# Display70_Cape.net
KiCad netlist of a schematic drawn in EAGLE
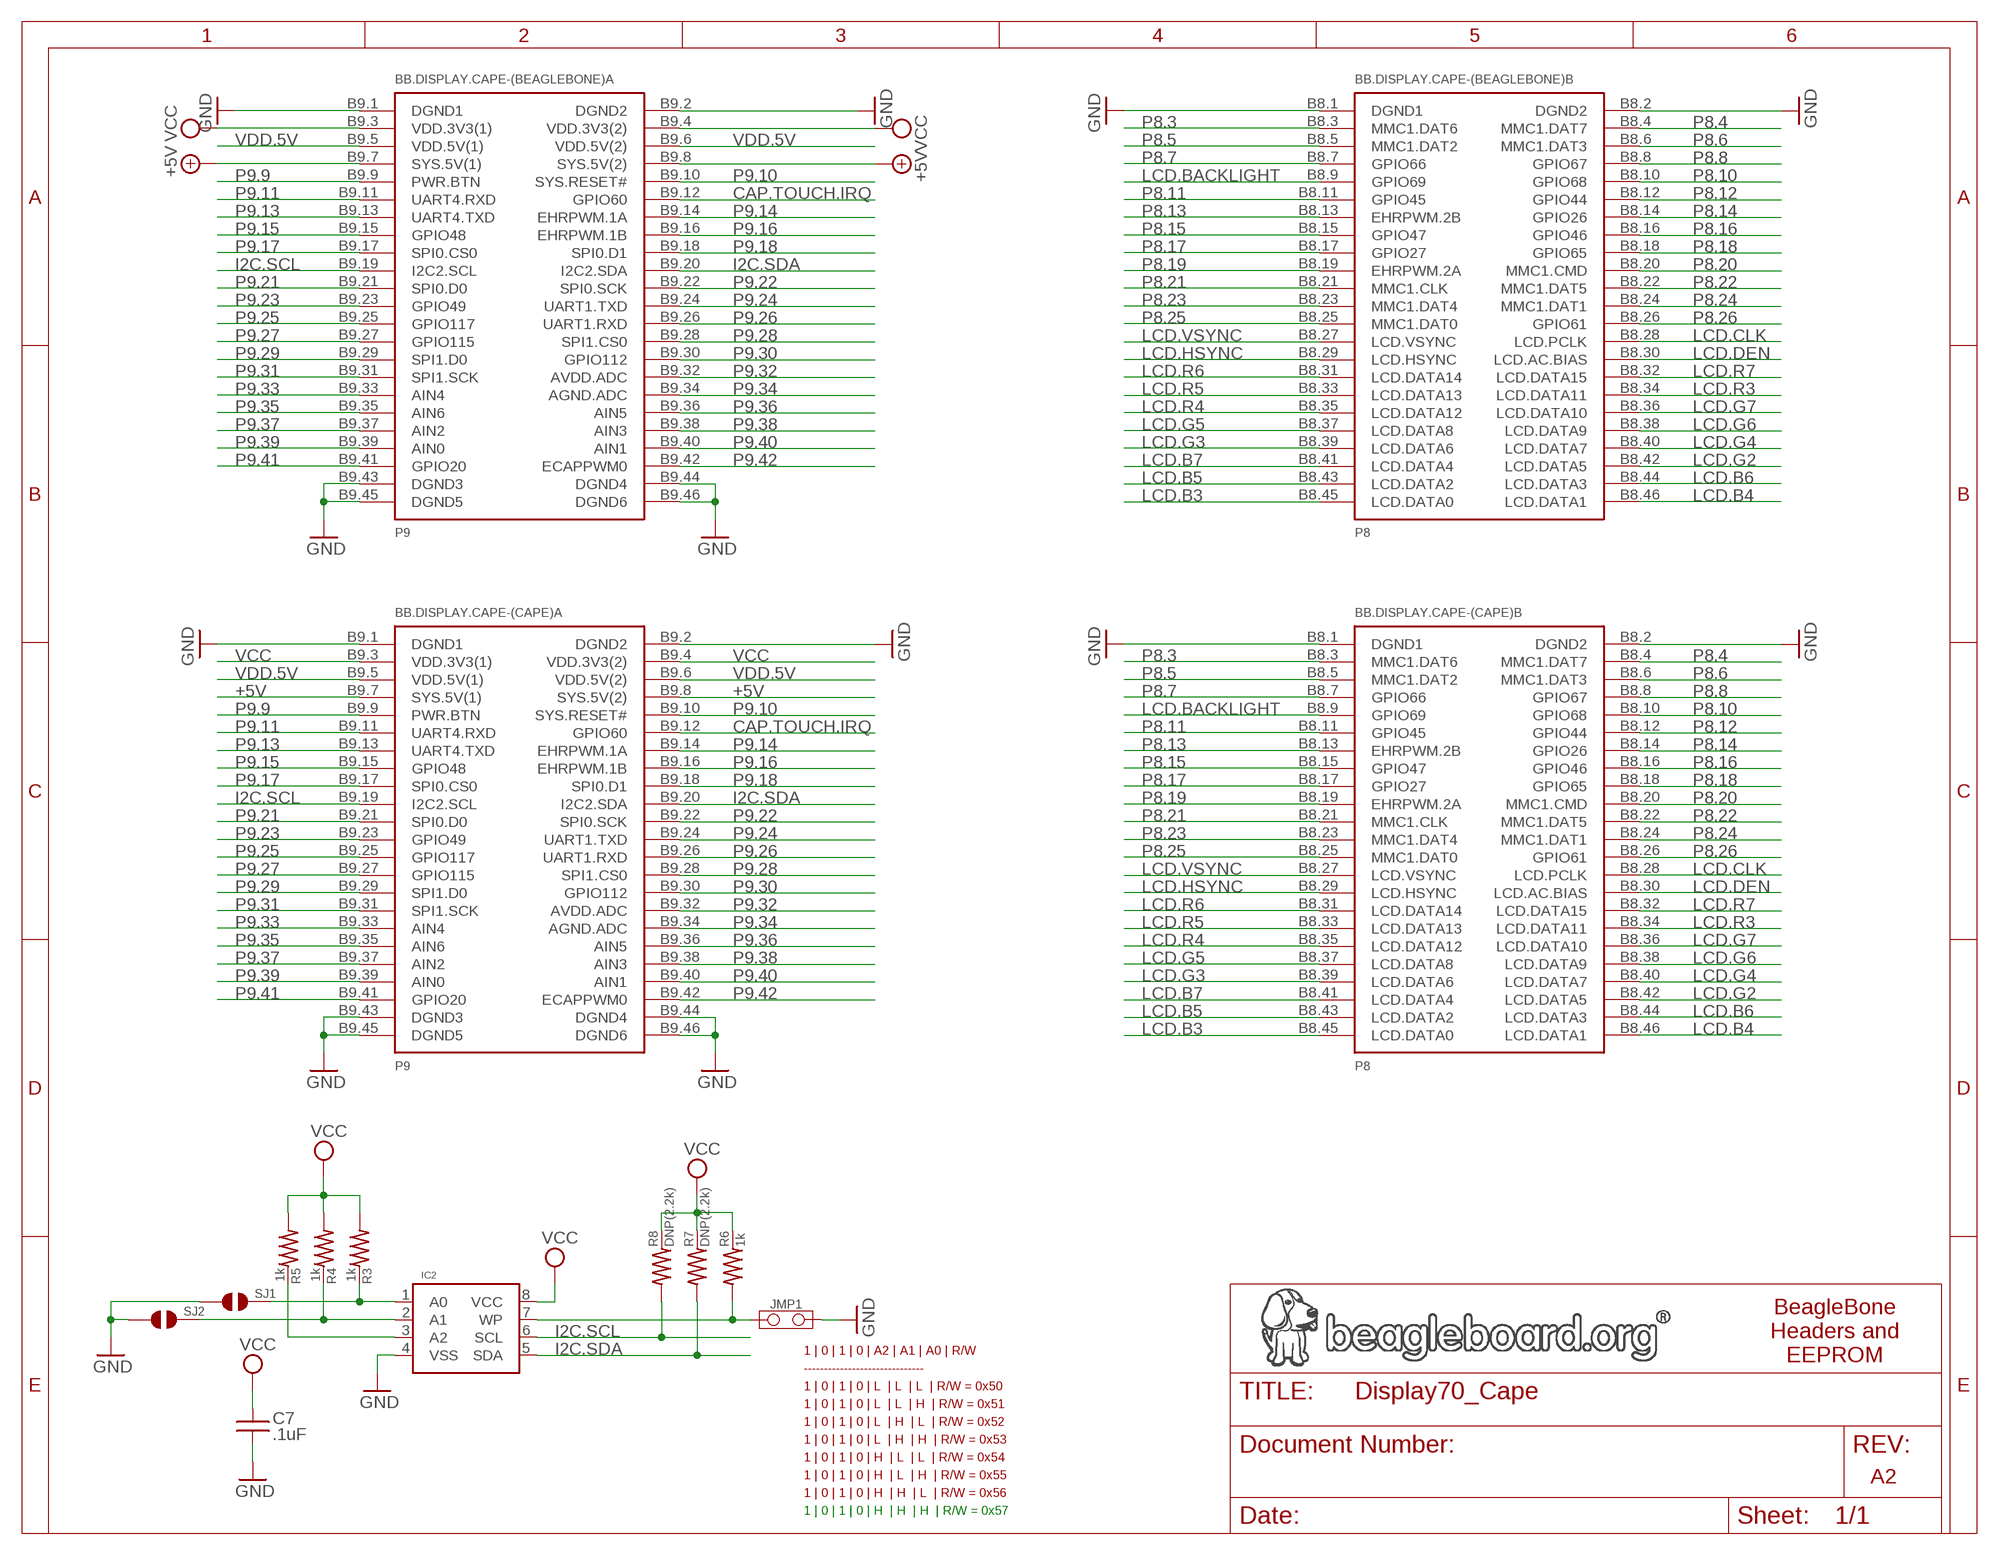
[diagram p0: schematic, sheet 1, part 1 of 2]
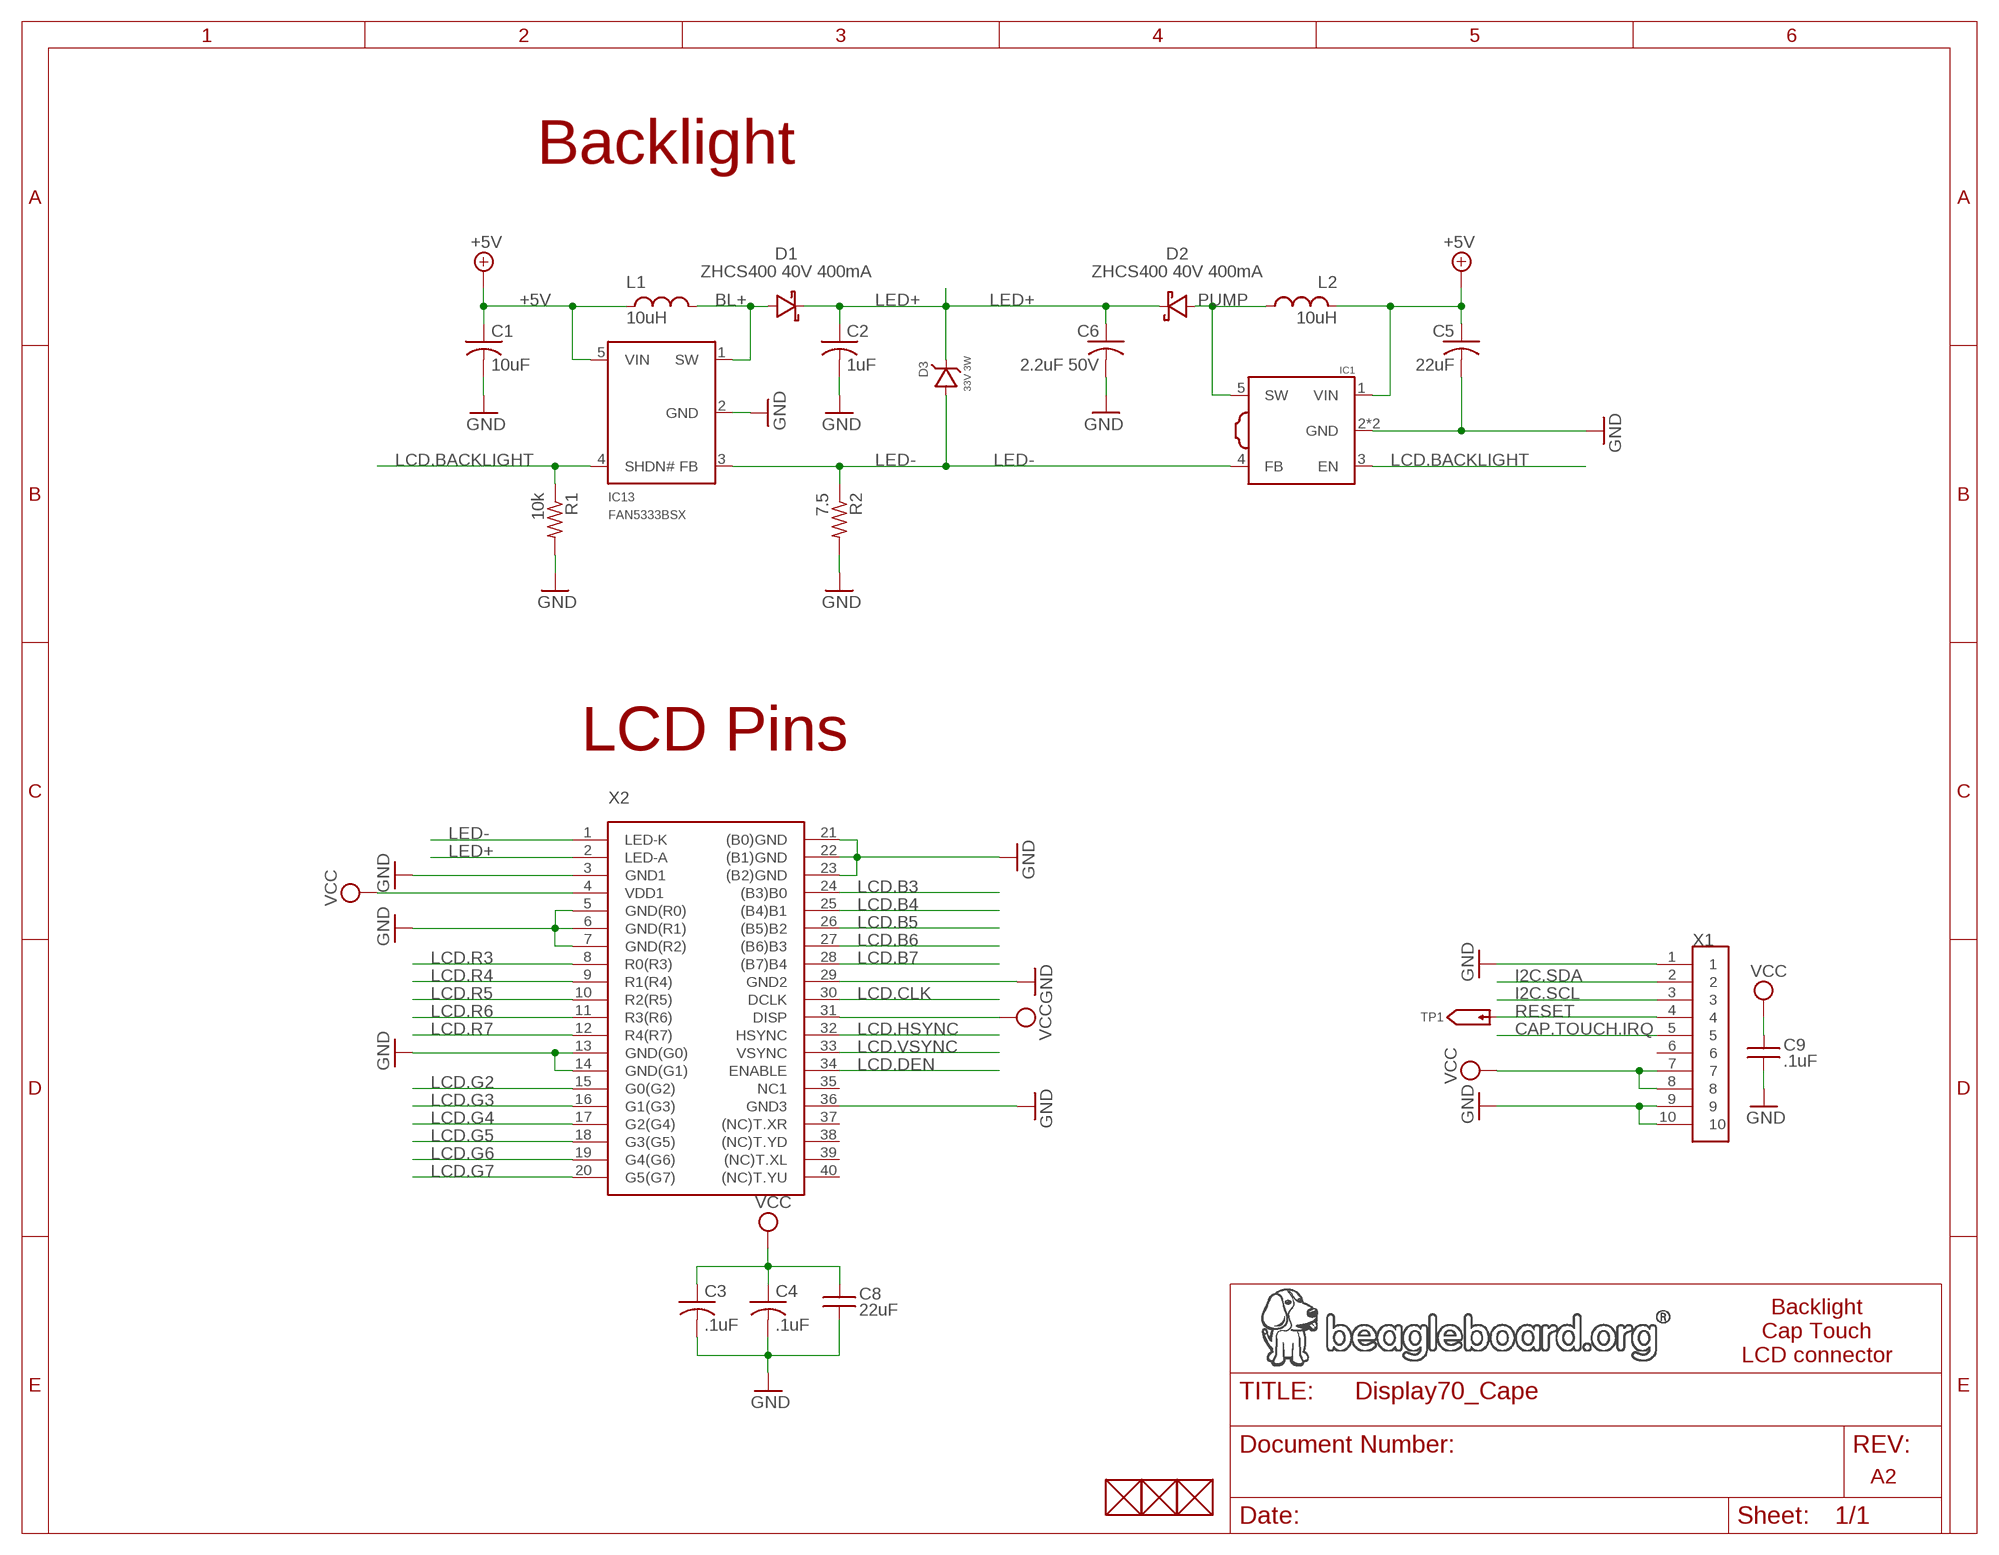
[diagram p1: schematic, sheet 1, part 2 of 2]

(export (version "E")
  (design (tool "Eeschema 10.0.6"))
  (components
    (comp (ref "BB.DISPLAY.CAPE-(BEAGLEBONE)")
      (value "BEAGLEBONE.CAPE.DISPLAY-7.BEAGLEBONE")
      (footprint "eagle-import:BEAGLEBONE.CAPE.DISPLAY-7.BEAGLEBONE")
      (libsource (lib "eagle-import") (part "BEAGLEBONE.CAPE.DISPLAY-7.BEAGLEBONE"))
    )
    (comp (ref "BB.DISPLAY.CAPE-(CAPE)")
      (value "BEAGLEBONE.CAPE.DISPLAY-7.CAPE")
      (footprint "eagle-import:BEAGLEBONE.CAPE.DISPLAY-7.CAPE")
      (libsource (lib "eagle-import") (part "BEAGLEBONE.CAPE.DISPLAY-7.CAPE"))
    )
    (comp (ref "C1")
      (value "10uF")
      (footprint "eagle-import:C0603K")
      (libsource (lib "eagle-import") (part "C-USC0603K"))
    )
    (comp (ref "C2")
      (value "1uF")
      (footprint "eagle-import:C0805K")
      (libsource (lib "eagle-import") (part "C-USC0805K"))
    )
    (comp (ref "C3")
      (value ".1uF")
      (footprint "eagle-import:C0402K")
      (libsource (lib "eagle-import") (part "C-USC0402K"))
    )
    (comp (ref "C4")
      (value ".1uF")
      (footprint "eagle-import:C0402K")
      (libsource (lib "eagle-import") (part "C-USC0402K"))
    )
    (comp (ref "C5")
      (value "22uF")
      (footprint "eagle-import:C0805K")
      (libsource (lib "eagle-import") (part "C-USC0805K"))
    )
    (comp (ref "C6")
      (value "2.2uF 50V")
      (footprint "eagle-import:C0805K")
      (libsource (lib "eagle-import") (part "C-USC0805K"))
    )
    (comp (ref "C7")
      (value ".1uF")
      (footprint "eagle-import:0402")
      (libsource (lib "eagle-import") (part "CAPACITOR-(INCH)-0402"))
    )
    (comp (ref "C8")
      (value "22uF")
      (footprint "eagle-import:0805")
      (libsource (lib "eagle-import") (part "CAPACITOR-(INCH)-0805"))
    )
    (comp (ref "C9")
      (value ".1uF")
      (footprint "eagle-import:0402")
      (libsource (lib "eagle-import") (part "CAPACITOR-(INCH)-0402"))
    )
    (comp (ref "D1")
      (value "ZHCS400 40V 400mA")
      (footprint "eagle-import:SOD323(NXP)WAVE")
      (libsource (lib "eagle-import") (part "DIODE-SCHOTTKY-(NXP)-SOD323-(WAVE)"))
    )
    (comp (ref "D2")
      (value "ZHCS400 40V 400mA")
      (footprint "eagle-import:SOD323(NXP)WAVE")
      (libsource (lib "eagle-import") (part "DIODE-SCHOTTKY-(NXP)-SOD323-(WAVE)"))
    )
    (comp (ref "D3")
      (value "33V 3W")
      (footprint "eagle-import:SMB(ON.SEMI)")
      (libsource (lib "eagle-import") (part "DIODE-ZENER-"))
    )
    (comp (ref "FUD1")
      (value "FIDUCIAL")
      (footprint "eagle-import:FIDUCIAL_40MIL")
      (libsource (lib "eagle-import") (part "FIDUCIAL"))
    )
    (comp (ref "FUD2")
      (value "FIDUCIAL")
      (footprint "eagle-import:FIDUCIAL_40MIL")
      (libsource (lib "eagle-import") (part "FIDUCIAL"))
    )
    (comp (ref "FUD3")
      (value "FIDUCIAL")
      (footprint "eagle-import:FIDUCIAL_40MIL")
      (libsource (lib "eagle-import") (part "FIDUCIAL"))
    )
    (comp (ref "IC1")
      (value "PT4110")
      (footprint "eagle-import:SOT89-5(DIODES)")
      (libsource (lib "eagle-import") (part "PT4110"))
    )
    (comp (ref "IC2")
      (value "CAT24C32")
      (footprint "eagle-import:UDFN8,2X3(ON-SEMI)")
      (libsource (lib "eagle-import") (part "CAT24C32"))
    )
    (comp (ref "IC13")
      (value "FAN5333BSX")
      (footprint "eagle-import:SOT23-5(FAIRCHILD)")
      (libsource (lib "eagle-import") (part "FAN533X"))
    )
    (comp (ref "JMP1")
      (value "JUMPER-(X2)")
      (footprint "eagle-import:JUMPER-(X2)")
      (libsource (lib "eagle-import") (part "JUMPER-(X2)"))
    )
    (comp (ref "L1")
      (value "10uH")
      (footprint "eagle-import:NRS(TAIYO.YUDEN)")
      (libsource (lib "eagle-import") (part "INDUCTOR-(TAIYO-YUDEN)-NRS5030"))
    )
    (comp (ref "L2")
      (value "10uH")
      (footprint "eagle-import:NRS(TAIYO.YUDEN)")
      (libsource (lib "eagle-import") (part "INDUCTOR-(TAIYO-YUDEN)-NRS5030"))
    )
    (comp (ref "R1")
      (value "10k")
      (footprint "eagle-import:R0603")
      (libsource (lib "eagle-import") (part "R-US_R0603"))
    )
    (comp (ref "R2")
      (value "7.5")
      (footprint "eagle-import:R0603")
      (libsource (lib "eagle-import") (part "R-US_R0603"))
    )
    (comp (ref "R3")
      (value "1k")
      (footprint "eagle-import:0402")
      (libsource (lib "eagle-import") (part "RESISTOR-(INCH)-0402"))
    )
    (comp (ref "R4")
      (value "1k")
      (footprint "eagle-import:0402")
      (libsource (lib "eagle-import") (part "RESISTOR-(INCH)-0402"))
    )
    (comp (ref "R5")
      (value "1k")
      (footprint "eagle-import:0402")
      (libsource (lib "eagle-import") (part "RESISTOR-(INCH)-0402"))
    )
    (comp (ref "R6")
      (value "1k")
      (footprint "eagle-import:0402")
      (libsource (lib "eagle-import") (part "RESISTOR-(INCH)-0402"))
    )
    (comp (ref "R7")
      (value "DNP(2.2k)")
      (footprint "eagle-import:0402")
      (libsource (lib "eagle-import") (part "RESISTOR-(INCH)-0402"))
    )
    (comp (ref "R8")
      (value "DNP(2.2k)")
      (footprint "eagle-import:0402")
      (libsource (lib "eagle-import") (part "RESISTOR-(INCH)-0402"))
    )
    (comp (ref "SJ1")
      (value "SOLDER.JOINT-(INCH)-0402")
      (footprint "eagle-import:SOLDER.JOINT(0402)")
      (libsource (lib "eagle-import") (part "SOLDER.JOINT-(INCH)-0402"))
    )
    (comp (ref "SJ2")
      (value "SOLDER.JOINT-(INCH)-0402")
      (footprint "eagle-import:SOLDER.JOINT(0402)")
      (libsource (lib "eagle-import") (part "SOLDER.JOINT-(INCH)-0402"))
    )
    (comp (ref "TP1")
      (value "TESTPAD/W_HOLE_1X1")
      (footprint "eagle-import:TESTPAD_W_HOLE_1X1")
      (libsource (lib "eagle-import") (part "TESTPAD/W_HOLE_1X1"))
    )
    (comp (ref "X1")
      (value "10-PIN-(0.5MM-PITCH)-FPC-CONNECTOR")
      (footprint "eagle-import:10-PIN-(0.5MM-PITCH)-FPC-CONNECTOR")
      (libsource (lib "eagle-import") (part "10-PIN-(0.5MM-PITCH)-FPC-CONNECTOR"))
    )
    (comp (ref "X2")
      (value "LCD-40PIN_FFC/FPC_0.5MM_PITCH")
      (footprint "eagle-import:KISD04-40_T1_E")
      (libsource (lib "eagle-import") (part "LCD-40PIN_FFC/FPC_0.5MM_PITCH"))
    )
  )
  (nets
    (net (code "1") (name "+5V") (class "Default")
      (node (ref "BB.DISPLAY.CAPE-(BEAGLEBONE)") (pin "B9.7") (pinfunction "SYS.5V(1)_B9.7") (pintype "bidirectional"))
      (node (ref "BB.DISPLAY.CAPE-(BEAGLEBONE)") (pin "B9.8") (pinfunction "SYS.5V(2)_B9.8") (pintype "bidirectional"))
      (node (ref "BB.DISPLAY.CAPE-(CAPE)") (pin "B9.7") (pinfunction "SYS.5V(1)_B9.7") (pintype "bidirectional"))
      (node (ref "BB.DISPLAY.CAPE-(CAPE)") (pin "B9.8") (pinfunction "SYS.5V(2)_B9.8") (pintype "bidirectional"))
      (node (ref "C1") (pin "1") (pinfunction "1_1") (pintype "passive"))
      (node (ref "C5") (pin "1") (pinfunction "1_1") (pintype "passive"))
      (node (ref "IC1") (pin "1") (pinfunction "VIN_1") (pintype "bidirectional"))
      (node (ref "IC13") (pin "5") (pinfunction "VIN_5") (pintype "bidirectional"))
      (node (ref "L1") (pin "1") (pinfunction "1_1") (pintype "bidirectional"))
      (node (ref "L2") (pin "1") (pinfunction "1_1") (pintype "bidirectional"))
    )
    (net (code "2") (name "/BL+") (class "Default")
      (node (ref "D1") (pin "A") (pinfunction "ANODE_A") (pintype "bidirectional"))
      (node (ref "IC13") (pin "1") (pinfunction "SW_1") (pintype "bidirectional"))
      (node (ref "L1") (pin "2") (pinfunction "2_2") (pintype "bidirectional"))
    )
    (net (code "3") (name "/CAP.TOUCH.IRQ") (class "Default")
      (node (ref "BB.DISPLAY.CAPE-(BEAGLEBONE)") (pin "B9.12") (pinfunction "GPIO60_B9.12") (pintype "bidirectional"))
      (node (ref "BB.DISPLAY.CAPE-(CAPE)") (pin "B9.12") (pinfunction "GPIO60_B9.12") (pintype "bidirectional"))
      (node (ref "X1") (pin "5") (pinfunction "5_5") (pintype "bidirectional"))
    )
    (net (code "4") (name "/I2C.SCL") (class "Default")
      (node (ref "BB.DISPLAY.CAPE-(BEAGLEBONE)") (pin "B9.19") (pinfunction "I2C2.SCL_B9.19") (pintype "bidirectional"))
      (node (ref "BB.DISPLAY.CAPE-(CAPE)") (pin "B9.19") (pinfunction "I2C2.SCL_B9.19") (pintype "bidirectional"))
      (node (ref "IC2") (pin "6") (pinfunction "SCL_6") (pintype "bidirectional"))
      (node (ref "R8") (pin "1") (pinfunction "1_1") (pintype "bidirectional"))
      (node (ref "X1") (pin "3") (pinfunction "3_3") (pintype "bidirectional"))
    )
    (net (code "5") (name "/I2C.SDA") (class "Default")
      (node (ref "BB.DISPLAY.CAPE-(BEAGLEBONE)") (pin "B9.20") (pinfunction "I2C2.SDA_B9.20") (pintype "bidirectional"))
      (node (ref "BB.DISPLAY.CAPE-(CAPE)") (pin "B9.20") (pinfunction "I2C2.SDA_B9.20") (pintype "bidirectional"))
      (node (ref "IC2") (pin "5") (pinfunction "SDA_5") (pintype "bidirectional"))
      (node (ref "R7") (pin "1") (pinfunction "1_1") (pintype "bidirectional"))
      (node (ref "X1") (pin "2") (pinfunction "2_2") (pintype "bidirectional"))
    )
    (net (code "6") (name "/LCD.B3") (class "Default")
      (node (ref "BB.DISPLAY.CAPE-(BEAGLEBONE)") (pin "B8.45") (pinfunction "LCD.DATA0_B8.45") (pintype "bidirectional"))
      (node (ref "BB.DISPLAY.CAPE-(CAPE)") (pin "B8.45") (pinfunction "LCD.DATA0_B8.45") (pintype "bidirectional"))
      (node (ref "X2") (pin "24") (pinfunction "(B3)B0_24") (pintype "bidirectional"))
    )
    (net (code "7") (name "/LCD.B4") (class "Default")
      (node (ref "BB.DISPLAY.CAPE-(BEAGLEBONE)") (pin "B8.46") (pinfunction "LCD.DATA1_B8.46") (pintype "bidirectional"))
      (node (ref "BB.DISPLAY.CAPE-(CAPE)") (pin "B8.46") (pinfunction "LCD.DATA1_B8.46") (pintype "bidirectional"))
      (node (ref "X2") (pin "25") (pinfunction "(B4)B1_25") (pintype "bidirectional"))
    )
    (net (code "8") (name "/LCD.B5") (class "Default")
      (node (ref "BB.DISPLAY.CAPE-(BEAGLEBONE)") (pin "B8.43") (pinfunction "LCD.DATA2_B8.43") (pintype "bidirectional"))
      (node (ref "BB.DISPLAY.CAPE-(CAPE)") (pin "B8.43") (pinfunction "LCD.DATA2_B8.43") (pintype "bidirectional"))
      (node (ref "X2") (pin "26") (pinfunction "(B5)B2_26") (pintype "bidirectional"))
    )
    (net (code "9") (name "/LCD.B6") (class "Default")
      (node (ref "BB.DISPLAY.CAPE-(BEAGLEBONE)") (pin "B8.44") (pinfunction "LCD.DATA3_B8.44") (pintype "bidirectional"))
      (node (ref "BB.DISPLAY.CAPE-(CAPE)") (pin "B8.44") (pinfunction "LCD.DATA3_B8.44") (pintype "bidirectional"))
      (node (ref "X2") (pin "27") (pinfunction "(B6)B3_27") (pintype "bidirectional"))
    )
    (net (code "10") (name "/LCD.B7") (class "Default")
      (node (ref "BB.DISPLAY.CAPE-(BEAGLEBONE)") (pin "B8.41") (pinfunction "LCD.DATA4_B8.41") (pintype "bidirectional"))
      (node (ref "BB.DISPLAY.CAPE-(CAPE)") (pin "B8.41") (pinfunction "LCD.DATA4_B8.41") (pintype "bidirectional"))
      (node (ref "X2") (pin "28") (pinfunction "(B7)B4_28") (pintype "bidirectional"))
    )
    (net (code "11") (name "/LCD.BACKLIGHT") (class "Default")
      (node (ref "BB.DISPLAY.CAPE-(BEAGLEBONE)") (pin "B8.9") (pinfunction "GPIO69_B8.9") (pintype "bidirectional"))
      (node (ref "BB.DISPLAY.CAPE-(CAPE)") (pin "B8.9") (pinfunction "GPIO69_B8.9") (pintype "bidirectional"))
      (node (ref "IC1") (pin "3") (pinfunction "EN_3") (pintype "bidirectional"))
      (node (ref "IC13") (pin "4") (pinfunction "SHDN#_4") (pintype "bidirectional"))
      (node (ref "R1") (pin "1") (pinfunction "1_1") (pintype "passive"))
    )
    (net (code "12") (name "/LCD.CLK") (class "Default")
      (node (ref "BB.DISPLAY.CAPE-(BEAGLEBONE)") (pin "B8.28") (pinfunction "LCD.PCLK_B8.28") (pintype "bidirectional"))
      (node (ref "BB.DISPLAY.CAPE-(CAPE)") (pin "B8.28") (pinfunction "LCD.PCLK_B8.28") (pintype "bidirectional"))
      (node (ref "X2") (pin "30") (pinfunction "DCLK_30") (pintype "bidirectional"))
    )
    (net (code "13") (name "/LCD.DEN") (class "Default")
      (node (ref "BB.DISPLAY.CAPE-(BEAGLEBONE)") (pin "B8.30") (pinfunction "LCD.AC.BIAS_B8.30") (pintype "bidirectional"))
      (node (ref "BB.DISPLAY.CAPE-(CAPE)") (pin "B8.30") (pinfunction "LCD.AC.BIAS_B8.30") (pintype "bidirectional"))
      (node (ref "X2") (pin "34") (pinfunction "ENABLE_34") (pintype "bidirectional"))
    )
    (net (code "14") (name "/LCD.G2") (class "Default")
      (node (ref "BB.DISPLAY.CAPE-(BEAGLEBONE)") (pin "B8.42") (pinfunction "LCD.DATA5_B8.42") (pintype "bidirectional"))
      (node (ref "BB.DISPLAY.CAPE-(CAPE)") (pin "B8.42") (pinfunction "LCD.DATA5_B8.42") (pintype "bidirectional"))
      (node (ref "X2") (pin "15") (pinfunction "G0(G2)_15") (pintype "bidirectional"))
    )
    (net (code "15") (name "/LCD.G3") (class "Default")
      (node (ref "BB.DISPLAY.CAPE-(BEAGLEBONE)") (pin "B8.39") (pinfunction "LCD.DATA6_B8.39") (pintype "bidirectional"))
      (node (ref "BB.DISPLAY.CAPE-(CAPE)") (pin "B8.39") (pinfunction "LCD.DATA6_B8.39") (pintype "bidirectional"))
      (node (ref "X2") (pin "16") (pinfunction "G1(G3)_16") (pintype "bidirectional"))
    )
    (net (code "16") (name "/LCD.G4") (class "Default")
      (node (ref "BB.DISPLAY.CAPE-(BEAGLEBONE)") (pin "B8.40") (pinfunction "LCD.DATA7_B8.40") (pintype "bidirectional"))
      (node (ref "BB.DISPLAY.CAPE-(CAPE)") (pin "B8.40") (pinfunction "LCD.DATA7_B8.40") (pintype "bidirectional"))
      (node (ref "X2") (pin "17") (pinfunction "G2(G4)_17") (pintype "bidirectional"))
    )
    (net (code "17") (name "/LCD.G5") (class "Default")
      (node (ref "BB.DISPLAY.CAPE-(BEAGLEBONE)") (pin "B8.37") (pinfunction "LCD.DATA8_B8.37") (pintype "bidirectional"))
      (node (ref "BB.DISPLAY.CAPE-(CAPE)") (pin "B8.37") (pinfunction "LCD.DATA8_B8.37") (pintype "bidirectional"))
      (node (ref "X2") (pin "18") (pinfunction "G3(G5)_18") (pintype "bidirectional"))
    )
    (net (code "18") (name "/LCD.G6") (class "Default")
      (node (ref "BB.DISPLAY.CAPE-(BEAGLEBONE)") (pin "B8.38") (pinfunction "LCD.DATA9_B8.38") (pintype "bidirectional"))
      (node (ref "BB.DISPLAY.CAPE-(CAPE)") (pin "B8.38") (pinfunction "LCD.DATA9_B8.38") (pintype "bidirectional"))
      (node (ref "X2") (pin "19") (pinfunction "G4(G6)_19") (pintype "bidirectional"))
    )
    (net (code "19") (name "/LCD.G7") (class "Default")
      (node (ref "BB.DISPLAY.CAPE-(BEAGLEBONE)") (pin "B8.36") (pinfunction "LCD.DATA10_B8.36") (pintype "bidirectional"))
      (node (ref "BB.DISPLAY.CAPE-(CAPE)") (pin "B8.36") (pinfunction "LCD.DATA10_B8.36") (pintype "bidirectional"))
      (node (ref "X2") (pin "20") (pinfunction "G5(G7)_20") (pintype "bidirectional"))
    )
    (net (code "20") (name "/LCD.HSYNC") (class "Default")
      (node (ref "BB.DISPLAY.CAPE-(BEAGLEBONE)") (pin "B8.29") (pinfunction "LCD.HSYNC_B8.29") (pintype "bidirectional"))
      (node (ref "BB.DISPLAY.CAPE-(CAPE)") (pin "B8.29") (pinfunction "LCD.HSYNC_B8.29") (pintype "bidirectional"))
      (node (ref "X2") (pin "32") (pinfunction "HSYNC_32") (pintype "bidirectional"))
    )
    (net (code "21") (name "/LCD.R3") (class "Default")
      (node (ref "BB.DISPLAY.CAPE-(BEAGLEBONE)") (pin "B8.34") (pinfunction "LCD.DATA11_B8.34") (pintype "bidirectional"))
      (node (ref "BB.DISPLAY.CAPE-(CAPE)") (pin "B8.34") (pinfunction "LCD.DATA11_B8.34") (pintype "bidirectional"))
      (node (ref "X2") (pin "8") (pinfunction "R0(R3)_8") (pintype "bidirectional"))
    )
    (net (code "22") (name "/LCD.R4") (class "Default")
      (node (ref "BB.DISPLAY.CAPE-(BEAGLEBONE)") (pin "B8.35") (pinfunction "LCD.DATA12_B8.35") (pintype "bidirectional"))
      (node (ref "BB.DISPLAY.CAPE-(CAPE)") (pin "B8.35") (pinfunction "LCD.DATA12_B8.35") (pintype "bidirectional"))
      (node (ref "X2") (pin "9") (pinfunction "R1(R4)_9") (pintype "bidirectional"))
    )
    (net (code "23") (name "/LCD.R5") (class "Default")
      (node (ref "BB.DISPLAY.CAPE-(BEAGLEBONE)") (pin "B8.33") (pinfunction "LCD.DATA13_B8.33") (pintype "bidirectional"))
      (node (ref "BB.DISPLAY.CAPE-(CAPE)") (pin "B8.33") (pinfunction "LCD.DATA13_B8.33") (pintype "bidirectional"))
      (node (ref "X2") (pin "10") (pinfunction "R2(R5)_10") (pintype "bidirectional"))
    )
    (net (code "24") (name "/LCD.R6") (class "Default")
      (node (ref "BB.DISPLAY.CAPE-(BEAGLEBONE)") (pin "B8.31") (pinfunction "LCD.DATA14_B8.31") (pintype "bidirectional"))
      (node (ref "BB.DISPLAY.CAPE-(CAPE)") (pin "B8.31") (pinfunction "LCD.DATA14_B8.31") (pintype "bidirectional"))
      (node (ref "X2") (pin "11") (pinfunction "R3(R6)_11") (pintype "bidirectional"))
    )
    (net (code "25") (name "/LCD.R7") (class "Default")
      (node (ref "BB.DISPLAY.CAPE-(BEAGLEBONE)") (pin "B8.32") (pinfunction "LCD.DATA15_B8.32") (pintype "bidirectional"))
      (node (ref "BB.DISPLAY.CAPE-(CAPE)") (pin "B8.32") (pinfunction "LCD.DATA15_B8.32") (pintype "bidirectional"))
      (node (ref "X2") (pin "12") (pinfunction "R4(R7)_12") (pintype "bidirectional"))
    )
    (net (code "26") (name "/LCD.VSYNC") (class "Default")
      (node (ref "BB.DISPLAY.CAPE-(BEAGLEBONE)") (pin "B8.27") (pinfunction "LCD.VSYNC_B8.27") (pintype "bidirectional"))
      (node (ref "BB.DISPLAY.CAPE-(CAPE)") (pin "B8.27") (pinfunction "LCD.VSYNC_B8.27") (pintype "bidirectional"))
      (node (ref "X2") (pin "33") (pinfunction "VSYNC_33") (pintype "bidirectional"))
    )
    (net (code "27") (name "/LED+") (class "Default")
      (node (ref "C2") (pin "1") (pinfunction "1_1") (pintype "passive"))
      (node (ref "C6") (pin "1") (pinfunction "1_1") (pintype "passive"))
      (node (ref "D1") (pin "C") (pinfunction "CATHODE_C") (pintype "bidirectional"))
      (node (ref "D2") (pin "C") (pinfunction "CATHODE_C") (pintype "bidirectional"))
      (node (ref "D3") (pin "K") (pinfunction "K_K") (pintype "bidirectional"))
      (node (ref "X2") (pin "2") (pinfunction "LED-A_2") (pintype "bidirectional"))
    )
    (net (code "28") (name "/LED-") (class "Default")
      (node (ref "D3") (pin "A") (pinfunction "A_A") (pintype "bidirectional"))
      (node (ref "IC1") (pin "4") (pinfunction "FB_4") (pintype "bidirectional"))
      (node (ref "IC13") (pin "3") (pinfunction "FB_3") (pintype "bidirectional"))
      (node (ref "R2") (pin "1") (pinfunction "1_1") (pintype "passive"))
      (node (ref "X2") (pin "1") (pinfunction "LED-K_1") (pintype "bidirectional"))
    )
    (net (code "29") (name "/P8.3") (class "Default")
      (node (ref "BB.DISPLAY.CAPE-(BEAGLEBONE)") (pin "B8.3") (pinfunction "MMC1.DAT6_B8.3") (pintype "bidirectional"))
      (node (ref "BB.DISPLAY.CAPE-(CAPE)") (pin "B8.3") (pinfunction "MMC1.DAT6_B8.3") (pintype "bidirectional"))
    )
    (net (code "30") (name "/P8.4") (class "Default")
      (node (ref "BB.DISPLAY.CAPE-(BEAGLEBONE)") (pin "B8.4") (pinfunction "MMC1.DAT7_B8.4") (pintype "bidirectional"))
      (node (ref "BB.DISPLAY.CAPE-(CAPE)") (pin "B8.4") (pinfunction "MMC1.DAT7_B8.4") (pintype "bidirectional"))
    )
    (net (code "31") (name "/P8.5") (class "Default")
      (node (ref "BB.DISPLAY.CAPE-(BEAGLEBONE)") (pin "B8.5") (pinfunction "MMC1.DAT2_B8.5") (pintype "bidirectional"))
      (node (ref "BB.DISPLAY.CAPE-(CAPE)") (pin "B8.5") (pinfunction "MMC1.DAT2_B8.5") (pintype "bidirectional"))
    )
    (net (code "32") (name "/P8.6") (class "Default")
      (node (ref "BB.DISPLAY.CAPE-(BEAGLEBONE)") (pin "B8.6") (pinfunction "MMC1.DAT3_B8.6") (pintype "bidirectional"))
      (node (ref "BB.DISPLAY.CAPE-(CAPE)") (pin "B8.6") (pinfunction "MMC1.DAT3_B8.6") (pintype "bidirectional"))
    )
    (net (code "33") (name "/P8.7") (class "Default")
      (node (ref "BB.DISPLAY.CAPE-(BEAGLEBONE)") (pin "B8.7") (pinfunction "GPIO66_B8.7") (pintype "bidirectional"))
      (node (ref "BB.DISPLAY.CAPE-(CAPE)") (pin "B8.7") (pinfunction "GPIO66_B8.7") (pintype "bidirectional"))
    )
    (net (code "34") (name "/P8.8") (class "Default")
      (node (ref "BB.DISPLAY.CAPE-(BEAGLEBONE)") (pin "B8.8") (pinfunction "GPIO67_B8.8") (pintype "bidirectional"))
      (node (ref "BB.DISPLAY.CAPE-(CAPE)") (pin "B8.8") (pinfunction "GPIO67_B8.8") (pintype "bidirectional"))
    )
    (net (code "35") (name "/P8.10") (class "Default")
      (node (ref "BB.DISPLAY.CAPE-(BEAGLEBONE)") (pin "B8.10") (pinfunction "GPIO68_B8.10") (pintype "bidirectional"))
      (node (ref "BB.DISPLAY.CAPE-(CAPE)") (pin "B8.10") (pinfunction "GPIO68_B8.10") (pintype "bidirectional"))
    )
    (net (code "36") (name "/P8.11") (class "Default")
      (node (ref "BB.DISPLAY.CAPE-(BEAGLEBONE)") (pin "B8.11") (pinfunction "GPIO45_B8.11") (pintype "bidirectional"))
      (node (ref "BB.DISPLAY.CAPE-(CAPE)") (pin "B8.11") (pinfunction "GPIO45_B8.11") (pintype "bidirectional"))
    )
    (net (code "37") (name "/P8.12") (class "Default")
      (node (ref "BB.DISPLAY.CAPE-(BEAGLEBONE)") (pin "B8.12") (pinfunction "GPIO44_B8.12") (pintype "bidirectional"))
      (node (ref "BB.DISPLAY.CAPE-(CAPE)") (pin "B8.12") (pinfunction "GPIO44_B8.12") (pintype "bidirectional"))
    )
    (net (code "38") (name "/P8.13") (class "Default")
      (node (ref "BB.DISPLAY.CAPE-(BEAGLEBONE)") (pin "B8.13") (pinfunction "EHRPWM.2B_B8.13") (pintype "bidirectional"))
      (node (ref "BB.DISPLAY.CAPE-(CAPE)") (pin "B8.13") (pinfunction "EHRPWM.2B_B8.13") (pintype "bidirectional"))
    )
    (net (code "39") (name "/P8.14") (class "Default")
      (node (ref "BB.DISPLAY.CAPE-(BEAGLEBONE)") (pin "B8.14") (pinfunction "GPIO26_B8.14") (pintype "bidirectional"))
      (node (ref "BB.DISPLAY.CAPE-(CAPE)") (pin "B8.14") (pinfunction "GPIO26_B8.14") (pintype "bidirectional"))
    )
    (net (code "40") (name "/P8.15") (class "Default")
      (node (ref "BB.DISPLAY.CAPE-(BEAGLEBONE)") (pin "B8.15") (pinfunction "GPIO47_B8.15") (pintype "bidirectional"))
      (node (ref "BB.DISPLAY.CAPE-(CAPE)") (pin "B8.15") (pinfunction "GPIO47_B8.15") (pintype "bidirectional"))
    )
    (net (code "41") (name "/P8.16") (class "Default")
      (node (ref "BB.DISPLAY.CAPE-(BEAGLEBONE)") (pin "B8.16") (pinfunction "GPIO46_B8.16") (pintype "bidirectional"))
      (node (ref "BB.DISPLAY.CAPE-(CAPE)") (pin "B8.16") (pinfunction "GPIO46_B8.16") (pintype "bidirectional"))
    )
    (net (code "42") (name "/P8.17") (class "Default")
      (node (ref "BB.DISPLAY.CAPE-(BEAGLEBONE)") (pin "B8.17") (pinfunction "GPIO27_B8.17") (pintype "bidirectional"))
      (node (ref "BB.DISPLAY.CAPE-(CAPE)") (pin "B8.17") (pinfunction "GPIO27_B8.17") (pintype "bidirectional"))
    )
    (net (code "43") (name "/P8.18") (class "Default")
      (node (ref "BB.DISPLAY.CAPE-(BEAGLEBONE)") (pin "B8.18") (pinfunction "GPIO65_B8.18") (pintype "bidirectional"))
      (node (ref "BB.DISPLAY.CAPE-(CAPE)") (pin "B8.18") (pinfunction "GPIO65_B8.18") (pintype "bidirectional"))
    )
    (net (code "44") (name "/P8.19") (class "Default")
      (node (ref "BB.DISPLAY.CAPE-(BEAGLEBONE)") (pin "B8.19") (pinfunction "EHRPWM.2A_B8.19") (pintype "bidirectional"))
      (node (ref "BB.DISPLAY.CAPE-(CAPE)") (pin "B8.19") (pinfunction "EHRPWM.2A_B8.19") (pintype "bidirectional"))
    )
    (net (code "45") (name "/P8.20") (class "Default")
      (node (ref "BB.DISPLAY.CAPE-(BEAGLEBONE)") (pin "B8.20") (pinfunction "MMC1.CMD_B8.20") (pintype "bidirectional"))
      (node (ref "BB.DISPLAY.CAPE-(CAPE)") (pin "B8.20") (pinfunction "MMC1.CMD_B8.20") (pintype "bidirectional"))
    )
    (net (code "46") (name "/P8.21") (class "Default")
      (node (ref "BB.DISPLAY.CAPE-(BEAGLEBONE)") (pin "B8.21") (pinfunction "MMC1.CLK_B8.21") (pintype "bidirectional"))
      (node (ref "BB.DISPLAY.CAPE-(CAPE)") (pin "B8.21") (pinfunction "MMC1.CLK_B8.21") (pintype "bidirectional"))
    )
    (net (code "47") (name "/P8.22") (class "Default")
      (node (ref "BB.DISPLAY.CAPE-(BEAGLEBONE)") (pin "B8.22") (pinfunction "MMC1.DAT5_B8.22") (pintype "bidirectional"))
      (node (ref "BB.DISPLAY.CAPE-(CAPE)") (pin "B8.22") (pinfunction "MMC1.DAT5_B8.22") (pintype "bidirectional"))
    )
    (net (code "48") (name "/P8.23") (class "Default")
      (node (ref "BB.DISPLAY.CAPE-(BEAGLEBONE)") (pin "B8.23") (pinfunction "MMC1.DAT4_B8.23") (pintype "bidirectional"))
      (node (ref "BB.DISPLAY.CAPE-(CAPE)") (pin "B8.23") (pinfunction "MMC1.DAT4_B8.23") (pintype "bidirectional"))
    )
    (net (code "49") (name "/P8.24") (class "Default")
      (node (ref "BB.DISPLAY.CAPE-(BEAGLEBONE)") (pin "B8.24") (pinfunction "MMC1.DAT1_B8.24") (pintype "bidirectional"))
      (node (ref "BB.DISPLAY.CAPE-(CAPE)") (pin "B8.24") (pinfunction "MMC1.DAT1_B8.24") (pintype "bidirectional"))
    )
    (net (code "50") (name "/P8.25") (class "Default")
      (node (ref "BB.DISPLAY.CAPE-(BEAGLEBONE)") (pin "B8.25") (pinfunction "MMC1.DAT0_B8.25") (pintype "bidirectional"))
      (node (ref "BB.DISPLAY.CAPE-(CAPE)") (pin "B8.25") (pinfunction "MMC1.DAT0_B8.25") (pintype "bidirectional"))
    )
    (net (code "51") (name "/P8.26") (class "Default")
      (node (ref "BB.DISPLAY.CAPE-(BEAGLEBONE)") (pin "B8.26") (pinfunction "GPIO61_B8.26") (pintype "bidirectional"))
      (node (ref "BB.DISPLAY.CAPE-(CAPE)") (pin "B8.26") (pinfunction "GPIO61_B8.26") (pintype "bidirectional"))
    )
    (net (code "52") (name "/P9.9") (class "Default")
      (node (ref "BB.DISPLAY.CAPE-(BEAGLEBONE)") (pin "B9.9") (pinfunction "PWR.BTN_B9.9") (pintype "bidirectional"))
      (node (ref "BB.DISPLAY.CAPE-(CAPE)") (pin "B9.9") (pinfunction "PWR.BTN_B9.9") (pintype "bidirectional"))
    )
    (net (code "53") (name "/P9.10") (class "Default")
      (node (ref "BB.DISPLAY.CAPE-(BEAGLEBONE)") (pin "B9.10") (pinfunction "SYS.RESET#_B9.10") (pintype "bidirectional"))
      (node (ref "BB.DISPLAY.CAPE-(CAPE)") (pin "B9.10") (pinfunction "SYS.RESET#_B9.10") (pintype "bidirectional"))
    )
    (net (code "54") (name "/P9.11") (class "Default")
      (node (ref "BB.DISPLAY.CAPE-(BEAGLEBONE)") (pin "B9.11") (pinfunction "UART4.RXD_B9.11") (pintype "bidirectional"))
      (node (ref "BB.DISPLAY.CAPE-(CAPE)") (pin "B9.11") (pinfunction "UART4.RXD_B9.11") (pintype "bidirectional"))
    )
    (net (code "55") (name "/P9.13") (class "Default")
      (node (ref "BB.DISPLAY.CAPE-(BEAGLEBONE)") (pin "B9.13") (pinfunction "UART4.TXD_B9.13") (pintype "bidirectional"))
      (node (ref "BB.DISPLAY.CAPE-(CAPE)") (pin "B9.13") (pinfunction "UART4.TXD_B9.13") (pintype "bidirectional"))
    )
    (net (code "56") (name "/P9.14") (class "Default")
      (node (ref "BB.DISPLAY.CAPE-(BEAGLEBONE)") (pin "B9.14") (pinfunction "EHRPWM.1A_B9.14") (pintype "bidirectional"))
      (node (ref "BB.DISPLAY.CAPE-(CAPE)") (pin "B9.14") (pinfunction "EHRPWM.1A_B9.14") (pintype "bidirectional"))
    )
    (net (code "57") (name "/P9.15") (class "Default")
      (node (ref "BB.DISPLAY.CAPE-(BEAGLEBONE)") (pin "B9.15") (pinfunction "GPIO48_B9.15") (pintype "bidirectional"))
      (node (ref "BB.DISPLAY.CAPE-(CAPE)") (pin "B9.15") (pinfunction "GPIO48_B9.15") (pintype "bidirectional"))
    )
    (net (code "58") (name "/P9.16") (class "Default")
      (node (ref "BB.DISPLAY.CAPE-(BEAGLEBONE)") (pin "B9.16") (pinfunction "EHRPWM.1B_B9.16") (pintype "bidirectional"))
      (node (ref "BB.DISPLAY.CAPE-(CAPE)") (pin "B9.16") (pinfunction "EHRPWM.1B_B9.16") (pintype "bidirectional"))
    )
    (net (code "59") (name "/P9.17") (class "Default")
      (node (ref "BB.DISPLAY.CAPE-(BEAGLEBONE)") (pin "B9.17") (pinfunction "SPI0.CS0_B9.17") (pintype "bidirectional"))
      (node (ref "BB.DISPLAY.CAPE-(CAPE)") (pin "B9.17") (pinfunction "SPI0.CS0_B9.17") (pintype "bidirectional"))
    )
    (net (code "60") (name "/P9.18") (class "Default")
      (node (ref "BB.DISPLAY.CAPE-(BEAGLEBONE)") (pin "B9.18") (pinfunction "SPI0.D1_B9.18") (pintype "bidirectional"))
      (node (ref "BB.DISPLAY.CAPE-(CAPE)") (pin "B9.18") (pinfunction "SPI0.D1_B9.18") (pintype "bidirectional"))
    )
    (net (code "61") (name "/P9.21") (class "Default")
      (node (ref "BB.DISPLAY.CAPE-(BEAGLEBONE)") (pin "B9.21") (pinfunction "SPI0.D0_B9.21") (pintype "bidirectional"))
      (node (ref "BB.DISPLAY.CAPE-(CAPE)") (pin "B9.21") (pinfunction "SPI0.D0_B9.21") (pintype "bidirectional"))
    )
    (net (code "62") (name "/P9.22") (class "Default")
      (node (ref "BB.DISPLAY.CAPE-(BEAGLEBONE)") (pin "B9.22") (pinfunction "SPI0.SCK_B9.22") (pintype "bidirectional"))
      (node (ref "BB.DISPLAY.CAPE-(CAPE)") (pin "B9.22") (pinfunction "SPI0.SCK_B9.22") (pintype "bidirectional"))
    )
    (net (code "63") (name "/P9.23") (class "Default")
      (node (ref "BB.DISPLAY.CAPE-(BEAGLEBONE)") (pin "B9.23") (pinfunction "GPIO49_B9.23") (pintype "bidirectional"))
      (node (ref "BB.DISPLAY.CAPE-(CAPE)") (pin "B9.23") (pinfunction "GPIO49_B9.23") (pintype "bidirectional"))
    )
    (net (code "64") (name "/P9.24") (class "Default")
      (node (ref "BB.DISPLAY.CAPE-(BEAGLEBONE)") (pin "B9.24") (pinfunction "UART1.TXD_B9.24") (pintype "bidirectional"))
      (node (ref "BB.DISPLAY.CAPE-(CAPE)") (pin "B9.24") (pinfunction "UART1.TXD_B9.24") (pintype "bidirectional"))
    )
    (net (code "65") (name "/P9.25") (class "Default")
      (node (ref "BB.DISPLAY.CAPE-(BEAGLEBONE)") (pin "B9.25") (pinfunction "GPIO117_B9.25") (pintype "bidirectional"))
      (node (ref "BB.DISPLAY.CAPE-(CAPE)") (pin "B9.25") (pinfunction "GPIO117_B9.25") (pintype "bidirectional"))
    )
    (net (code "66") (name "/P9.26") (class "Default")
      (node (ref "BB.DISPLAY.CAPE-(BEAGLEBONE)") (pin "B9.26") (pinfunction "UART1.RXD_B9.26") (pintype "bidirectional"))
      (node (ref "BB.DISPLAY.CAPE-(CAPE)") (pin "B9.26") (pinfunction "UART1.RXD_B9.26") (pintype "bidirectional"))
    )
    (net (code "67") (name "/P9.27") (class "Default")
      (node (ref "BB.DISPLAY.CAPE-(BEAGLEBONE)") (pin "B9.27") (pinfunction "GPIO115_B9.27") (pintype "bidirectional"))
      (node (ref "BB.DISPLAY.CAPE-(CAPE)") (pin "B9.27") (pinfunction "GPIO115_B9.27") (pintype "bidirectional"))
    )
    (net (code "68") (name "/P9.28") (class "Default")
      (node (ref "BB.DISPLAY.CAPE-(BEAGLEBONE)") (pin "B9.28") (pinfunction "SPI1.CS0_B9.28") (pintype "bidirectional"))
      (node (ref "BB.DISPLAY.CAPE-(CAPE)") (pin "B9.28") (pinfunction "SPI1.CS0_B9.28") (pintype "bidirectional"))
    )
    (net (code "69") (name "/P9.29") (class "Default")
      (node (ref "BB.DISPLAY.CAPE-(BEAGLEBONE)") (pin "B9.29") (pinfunction "SPI1.D0_B9.29") (pintype "bidirectional"))
      (node (ref "BB.DISPLAY.CAPE-(CAPE)") (pin "B9.29") (pinfunction "SPI1.D0_B9.29") (pintype "bidirectional"))
    )
    (net (code "70") (name "/P9.30") (class "Default")
      (node (ref "BB.DISPLAY.CAPE-(BEAGLEBONE)") (pin "B9.30") (pinfunction "GPIO112_B9.30") (pintype "bidirectional"))
      (node (ref "BB.DISPLAY.CAPE-(CAPE)") (pin "B9.30") (pinfunction "GPIO112_B9.30") (pintype "bidirectional"))
    )
    (net (code "71") (name "/P9.31") (class "Default")
      (node (ref "BB.DISPLAY.CAPE-(BEAGLEBONE)") (pin "B9.31") (pinfunction "SPI1.SCK_B9.31") (pintype "bidirectional"))
      (node (ref "BB.DISPLAY.CAPE-(CAPE)") (pin "B9.31") (pinfunction "SPI1.SCK_B9.31") (pintype "bidirectional"))
    )
    (net (code "72") (name "/P9.32") (class "Default")
      (node (ref "BB.DISPLAY.CAPE-(BEAGLEBONE)") (pin "B9.32") (pinfunction "AVDD.ADC_B9.32") (pintype "bidirectional"))
      (node (ref "BB.DISPLAY.CAPE-(CAPE)") (pin "B9.32") (pinfunction "AVDD.ADC_B9.32") (pintype "bidirectional"))
    )
    (net (code "73") (name "/P9.33") (class "Default")
      (node (ref "BB.DISPLAY.CAPE-(BEAGLEBONE)") (pin "B9.33") (pinfunction "AIN4_B9.33") (pintype "bidirectional"))
      (node (ref "BB.DISPLAY.CAPE-(CAPE)") (pin "B9.33") (pinfunction "AIN4_B9.33") (pintype "bidirectional"))
    )
    (net (code "74") (name "/P9.34") (class "Default")
      (node (ref "BB.DISPLAY.CAPE-(BEAGLEBONE)") (pin "B9.34") (pinfunction "AGND.ADC_B9.34") (pintype "bidirectional"))
      (node (ref "BB.DISPLAY.CAPE-(CAPE)") (pin "B9.34") (pinfunction "AGND.ADC_B9.34") (pintype "bidirectional"))
    )
    (net (code "75") (name "/P9.35") (class "Default")
      (node (ref "BB.DISPLAY.CAPE-(BEAGLEBONE)") (pin "B9.35") (pinfunction "AIN6_B9.35") (pintype "bidirectional"))
      (node (ref "BB.DISPLAY.CAPE-(CAPE)") (pin "B9.35") (pinfunction "AIN6_B9.35") (pintype "bidirectional"))
    )
    (net (code "76") (name "/P9.36") (class "Default")
      (node (ref "BB.DISPLAY.CAPE-(BEAGLEBONE)") (pin "B9.36") (pinfunction "AIN5_B9.36") (pintype "bidirectional"))
      (node (ref "BB.DISPLAY.CAPE-(CAPE)") (pin "B9.36") (pinfunction "AIN5_B9.36") (pintype "bidirectional"))
    )
    (net (code "77") (name "/P9.37") (class "Default")
      (node (ref "BB.DISPLAY.CAPE-(BEAGLEBONE)") (pin "B9.37") (pinfunction "AIN2_B9.37") (pintype "bidirectional"))
      (node (ref "BB.DISPLAY.CAPE-(CAPE)") (pin "B9.37") (pinfunction "AIN2_B9.37") (pintype "bidirectional"))
    )
    (net (code "78") (name "/P9.38") (class "Default")
      (node (ref "BB.DISPLAY.CAPE-(BEAGLEBONE)") (pin "B9.38") (pinfunction "AIN3_B9.38") (pintype "bidirectional"))
      (node (ref "BB.DISPLAY.CAPE-(CAPE)") (pin "B9.38") (pinfunction "AIN3_B9.38") (pintype "bidirectional"))
    )
    (net (code "79") (name "/P9.39") (class "Default")
      (node (ref "BB.DISPLAY.CAPE-(BEAGLEBONE)") (pin "B9.39") (pinfunction "AIN0_B9.39") (pintype "bidirectional"))
      (node (ref "BB.DISPLAY.CAPE-(CAPE)") (pin "B9.39") (pinfunction "AIN0_B9.39") (pintype "bidirectional"))
    )
    (net (code "80") (name "/P9.40") (class "Default")
      (node (ref "BB.DISPLAY.CAPE-(BEAGLEBONE)") (pin "B9.40") (pinfunction "AIN1_B9.40") (pintype "bidirectional"))
      (node (ref "BB.DISPLAY.CAPE-(CAPE)") (pin "B9.40") (pinfunction "AIN1_B9.40") (pintype "bidirectional"))
    )
    (net (code "81") (name "/P9.41") (class "Default")
      (node (ref "BB.DISPLAY.CAPE-(BEAGLEBONE)") (pin "B9.41") (pinfunction "GPIO20_B9.41") (pintype "bidirectional"))
      (node (ref "BB.DISPLAY.CAPE-(CAPE)") (pin "B9.41") (pinfunction "GPIO20_B9.41") (pintype "bidirectional"))
    )
    (net (code "82") (name "/P9.42") (class "Default")
      (node (ref "BB.DISPLAY.CAPE-(BEAGLEBONE)") (pin "B9.42") (pinfunction "ECAPPWM0_B9.42") (pintype "bidirectional"))
      (node (ref "BB.DISPLAY.CAPE-(CAPE)") (pin "B9.42") (pinfunction "ECAPPWM0_B9.42") (pintype "bidirectional"))
    )
    (net (code "83") (name "/PUMP") (class "Default")
      (node (ref "D2") (pin "A") (pinfunction "ANODE_A") (pintype "bidirectional"))
      (node (ref "IC1") (pin "5") (pinfunction "SW_5") (pintype "bidirectional"))
      (node (ref "L2") (pin "2") (pinfunction "2_2") (pintype "bidirectional"))
    )
    (net (code "84") (name "/RESET") (class "Default")
      (node (ref "TP1") (pin "P$1") (pinfunction "TP_P$1") (pintype "bidirectional"))
      (node (ref "X1") (pin "4") (pinfunction "4_4") (pintype "bidirectional"))
    )
    (net (code "85") (name "/VDD.5V") (class "Default")
      (node (ref "BB.DISPLAY.CAPE-(BEAGLEBONE)") (pin "B9.5") (pinfunction "VDD.5V(1)_B9.5") (pintype "bidirectional"))
      (node (ref "BB.DISPLAY.CAPE-(BEAGLEBONE)") (pin "B9.6") (pinfunction "VDD.5V(2)_B9.6") (pintype "bidirectional"))
      (node (ref "BB.DISPLAY.CAPE-(CAPE)") (pin "B9.5") (pinfunction "VDD.5V(1)_B9.5") (pintype "bidirectional"))
      (node (ref "BB.DISPLAY.CAPE-(CAPE)") (pin "B9.6") (pinfunction "VDD.5V(2)_B9.6") (pintype "bidirectional"))
    )
    (net (code "86") (name "GND") (class "Default")
      (node (ref "BB.DISPLAY.CAPE-(BEAGLEBONE)") (pin "B8.1") (pinfunction "DGND1_B8.1") (pintype "bidirectional"))
      (node (ref "BB.DISPLAY.CAPE-(BEAGLEBONE)") (pin "B8.2") (pinfunction "DGND2_B8.2") (pintype "bidirectional"))
      (node (ref "BB.DISPLAY.CAPE-(BEAGLEBONE)") (pin "B9.1") (pinfunction "DGND1_B9.1") (pintype "bidirectional"))
      (node (ref "BB.DISPLAY.CAPE-(BEAGLEBONE)") (pin "B9.2") (pinfunction "DGND2_B9.2") (pintype "bidirectional"))
      (node (ref "BB.DISPLAY.CAPE-(BEAGLEBONE)") (pin "B9.43") (pinfunction "DGND3_B9.43") (pintype "bidirectional"))
      (node (ref "BB.DISPLAY.CAPE-(BEAGLEBONE)") (pin "B9.44") (pinfunction "DGND4_B9.44") (pintype "bidirectional"))
      (node (ref "BB.DISPLAY.CAPE-(BEAGLEBONE)") (pin "B9.45") (pinfunction "DGND5_B9.45") (pintype "bidirectional"))
      (node (ref "BB.DISPLAY.CAPE-(BEAGLEBONE)") (pin "B9.46") (pinfunction "DGND6_B9.46") (pintype "bidirectional"))
      (node (ref "BB.DISPLAY.CAPE-(CAPE)") (pin "B8.1") (pinfunction "DGND1_B8.1") (pintype "bidirectional"))
      (node (ref "BB.DISPLAY.CAPE-(CAPE)") (pin "B8.2") (pinfunction "DGND2_B8.2") (pintype "bidirectional"))
      (node (ref "BB.DISPLAY.CAPE-(CAPE)") (pin "B9.1") (pinfunction "DGND1_B9.1") (pintype "bidirectional"))
      (node (ref "BB.DISPLAY.CAPE-(CAPE)") (pin "B9.2") (pinfunction "DGND2_B9.2") (pintype "bidirectional"))
      (node (ref "BB.DISPLAY.CAPE-(CAPE)") (pin "B9.43") (pinfunction "DGND3_B9.43") (pintype "bidirectional"))
      (node (ref "BB.DISPLAY.CAPE-(CAPE)") (pin "B9.44") (pinfunction "DGND4_B9.44") (pintype "bidirectional"))
      (node (ref "BB.DISPLAY.CAPE-(CAPE)") (pin "B9.45") (pinfunction "DGND5_B9.45") (pintype "bidirectional"))
      (node (ref "BB.DISPLAY.CAPE-(CAPE)") (pin "B9.46") (pinfunction "DGND6_B9.46") (pintype "bidirectional"))
      (node (ref "C1") (pin "2") (pinfunction "2_2") (pintype "passive"))
      (node (ref "C2") (pin "2") (pinfunction "2_2") (pintype "passive"))
      (node (ref "C3") (pin "2") (pinfunction "2_2") (pintype "passive"))
      (node (ref "C4") (pin "2") (pinfunction "2_2") (pintype "passive"))
      (node (ref "C5") (pin "2") (pinfunction "2_2") (pintype "passive"))
      (node (ref "C6") (pin "2") (pinfunction "2_2") (pintype "passive"))
      (node (ref "C7") (pin "2") (pinfunction "2_2") (pintype "bidirectional"))
      (node (ref "C8") (pin "2") (pinfunction "2_2") (pintype "bidirectional"))
      (node (ref "C9") (pin "2") (pinfunction "2_2") (pintype "bidirectional"))
      (node (ref "IC1") (pin "2") (pinfunction "GND_2") (pintype "bidirectional"))
      (node (ref "IC1") (pin "THERMAL") (pinfunction "GND_THERMAL") (pintype "bidirectional"))
      (node (ref "IC13") (pin "2") (pinfunction "GND_2") (pintype "bidirectional"))
      (node (ref "IC2") (pin "4") (pinfunction "VSS_4") (pintype "bidirectional"))
      (node (ref "JMP1") (pin "2") (pinfunction "2_2") (pintype "bidirectional"))
      (node (ref "R1") (pin "2") (pinfunction "2_2") (pintype "passive"))
      (node (ref "R2") (pin "2") (pinfunction "2_2") (pintype "passive"))
      (node (ref "SJ1") (pin "1") (pinfunction "1_1") (pintype "bidirectional"))
      (node (ref "SJ2") (pin "1") (pinfunction "1_1") (pintype "bidirectional"))
      (node (ref "X1") (pin "1") (pinfunction "1_1") (pintype "bidirectional"))
      (node (ref "X1") (pin "10") (pinfunction "10_10") (pintype "bidirectional"))
      (node (ref "X1") (pin "9") (pinfunction "9_9") (pintype "bidirectional"))
      (node (ref "X2") (pin "13") (pinfunction "GND(G0)_13") (pintype "bidirectional"))
      (node (ref "X2") (pin "14") (pinfunction "GND(G1)_14") (pintype "bidirectional"))
      (node (ref "X2") (pin "21") (pinfunction "(B0)GND_21") (pintype "bidirectional"))
      (node (ref "X2") (pin "22") (pinfunction "(B1)GND_22") (pintype "bidirectional"))
      (node (ref "X2") (pin "23") (pinfunction "(B2)GND_23") (pintype "bidirectional"))
      (node (ref "X2") (pin "29") (pinfunction "GND2_29") (pintype "bidirectional"))
      (node (ref "X2") (pin "3") (pinfunction "GND1_3") (pintype "bidirectional"))
      (node (ref "X2") (pin "36") (pinfunction "GND3_36") (pintype "bidirectional"))
      (node (ref "X2") (pin "5") (pinfunction "GND(R0)_5") (pintype "bidirectional"))
      (node (ref "X2") (pin "6") (pinfunction "GND(R1)_6") (pintype "bidirectional"))
      (node (ref "X2") (pin "7") (pinfunction "GND(R2)_7") (pintype "bidirectional"))
    )
    (net (code "87") (name "Net-(IC2-A0)") (class "Default")
      (node (ref "IC2") (pin "1") (pinfunction "A0_1") (pintype "bidirectional"))
      (node (ref "R3") (pin "2") (pinfunction "2_2") (pintype "bidirectional"))
      (node (ref "SJ1") (pin "2") (pinfunction "2_2") (pintype "bidirectional"))
    )
    (net (code "88") (name "Net-(IC2-A1)") (class "Default")
      (node (ref "IC2") (pin "2") (pinfunction "A1_2") (pintype "bidirectional"))
      (node (ref "R4") (pin "2") (pinfunction "2_2") (pintype "bidirectional"))
      (node (ref "SJ2") (pin "2") (pinfunction "2_2") (pintype "bidirectional"))
    )
    (net (code "89") (name "Net-(IC2-A2)") (class "Default")
      (node (ref "IC2") (pin "3") (pinfunction "A2_3") (pintype "bidirectional"))
      (node (ref "R5") (pin "2") (pinfunction "2_2") (pintype "bidirectional"))
    )
    (net (code "90") (name "Net-(IC2-WP)") (class "Default")
      (node (ref "IC2") (pin "7") (pinfunction "WP_7") (pintype "bidirectional"))
      (node (ref "JMP1") (pin "1") (pinfunction "1_1") (pintype "bidirectional"))
      (node (ref "R6") (pin "1") (pinfunction "1_1") (pintype "bidirectional"))
    )
    (net (code "91") (name "VCC") (class "Default")
      (node (ref "BB.DISPLAY.CAPE-(BEAGLEBONE)") (pin "B9.3") (pinfunction "VDD.3V3(1)_B9.3") (pintype "bidirectional"))
      (node (ref "BB.DISPLAY.CAPE-(BEAGLEBONE)") (pin "B9.4") (pinfunction "VDD.3V3(2)_B9.4") (pintype "bidirectional"))
      (node (ref "BB.DISPLAY.CAPE-(CAPE)") (pin "B9.3") (pinfunction "VDD.3V3(1)_B9.3") (pintype "bidirectional"))
      (node (ref "BB.DISPLAY.CAPE-(CAPE)") (pin "B9.4") (pinfunction "VDD.3V3(2)_B9.4") (pintype "bidirectional"))
      (node (ref "C3") (pin "1") (pinfunction "1_1") (pintype "passive"))
      (node (ref "C4") (pin "1") (pinfunction "1_1") (pintype "passive"))
      (node (ref "C7") (pin "1") (pinfunction "1_1") (pintype "bidirectional"))
      (node (ref "C8") (pin "1") (pinfunction "1_1") (pintype "bidirectional"))
      (node (ref "C9") (pin "1") (pinfunction "1_1") (pintype "bidirectional"))
      (node (ref "IC2") (pin "8") (pinfunction "VCC_8") (pintype "bidirectional"))
      (node (ref "R3") (pin "1") (pinfunction "1_1") (pintype "bidirectional"))
      (node (ref "R4") (pin "1") (pinfunction "1_1") (pintype "bidirectional"))
      (node (ref "R5") (pin "1") (pinfunction "1_1") (pintype "bidirectional"))
      (node (ref "R6") (pin "2") (pinfunction "2_2") (pintype "bidirectional"))
      (node (ref "R7") (pin "2") (pinfunction "2_2") (pintype "bidirectional"))
      (node (ref "R8") (pin "2") (pinfunction "2_2") (pintype "bidirectional"))
      (node (ref "X1") (pin "7") (pinfunction "7_7") (pintype "bidirectional"))
      (node (ref "X1") (pin "8") (pinfunction "8_8") (pintype "bidirectional"))
      (node (ref "X2") (pin "31") (pinfunction "DISP_31") (pintype "bidirectional"))
      (node (ref "X2") (pin "4") (pinfunction "VDD1_4") (pintype "bidirectional"))
    )
    (net (code "92") (name "unconnected-(FUD1-PadP$1)") (class "Default")
      (node (ref "FUD1") (pin "P$1") (pinfunction "P$1_P$1") (pintype "no_connect"))
    )
    (net (code "93") (name "unconnected-(FUD2-PadP$1)") (class "Default")
      (node (ref "FUD2") (pin "P$1") (pinfunction "P$1_P$1") (pintype "no_connect"))
    )
    (net (code "94") (name "unconnected-(FUD3-PadP$1)") (class "Default")
      (node (ref "FUD3") (pin "P$1") (pinfunction "P$1_P$1") (pintype "no_connect"))
    )
    (net (code "95") (name "unconnected-(X1-Pad6)") (class "Default")
      (node (ref "X1") (pin "6") (pinfunction "6_6") (pintype "bidirectional"))
    )
    (net (code "96") (name "unconnected-(X2-(NC)T.XL-Pad39)") (class "Default")
      (node (ref "X2") (pin "39") (pinfunction "(NC)T.XL_39") (pintype "bidirectional"))
    )
    (net (code "97") (name "unconnected-(X2-(NC)T.XR-Pad37)") (class "Default")
      (node (ref "X2") (pin "37") (pinfunction "(NC)T.XR_37") (pintype "bidirectional"))
    )
    (net (code "98") (name "unconnected-(X2-(NC)T.YD-Pad38)") (class "Default")
      (node (ref "X2") (pin "38") (pinfunction "(NC)T.YD_38") (pintype "bidirectional"))
    )
    (net (code "99") (name "unconnected-(X2-(NC)T.YU-Pad40)") (class "Default")
      (node (ref "X2") (pin "40") (pinfunction "(NC)T.YU_40") (pintype "bidirectional"))
    )
    (net (code "100") (name "unconnected-(X2-NC1-Pad35)") (class "Default")
      (node (ref "X2") (pin "35") (pinfunction "NC1_35") (pintype "bidirectional"))
    )
  )
)
